# Stiralka.net
KiCad netlist of a schematic drawn in Altium Designer
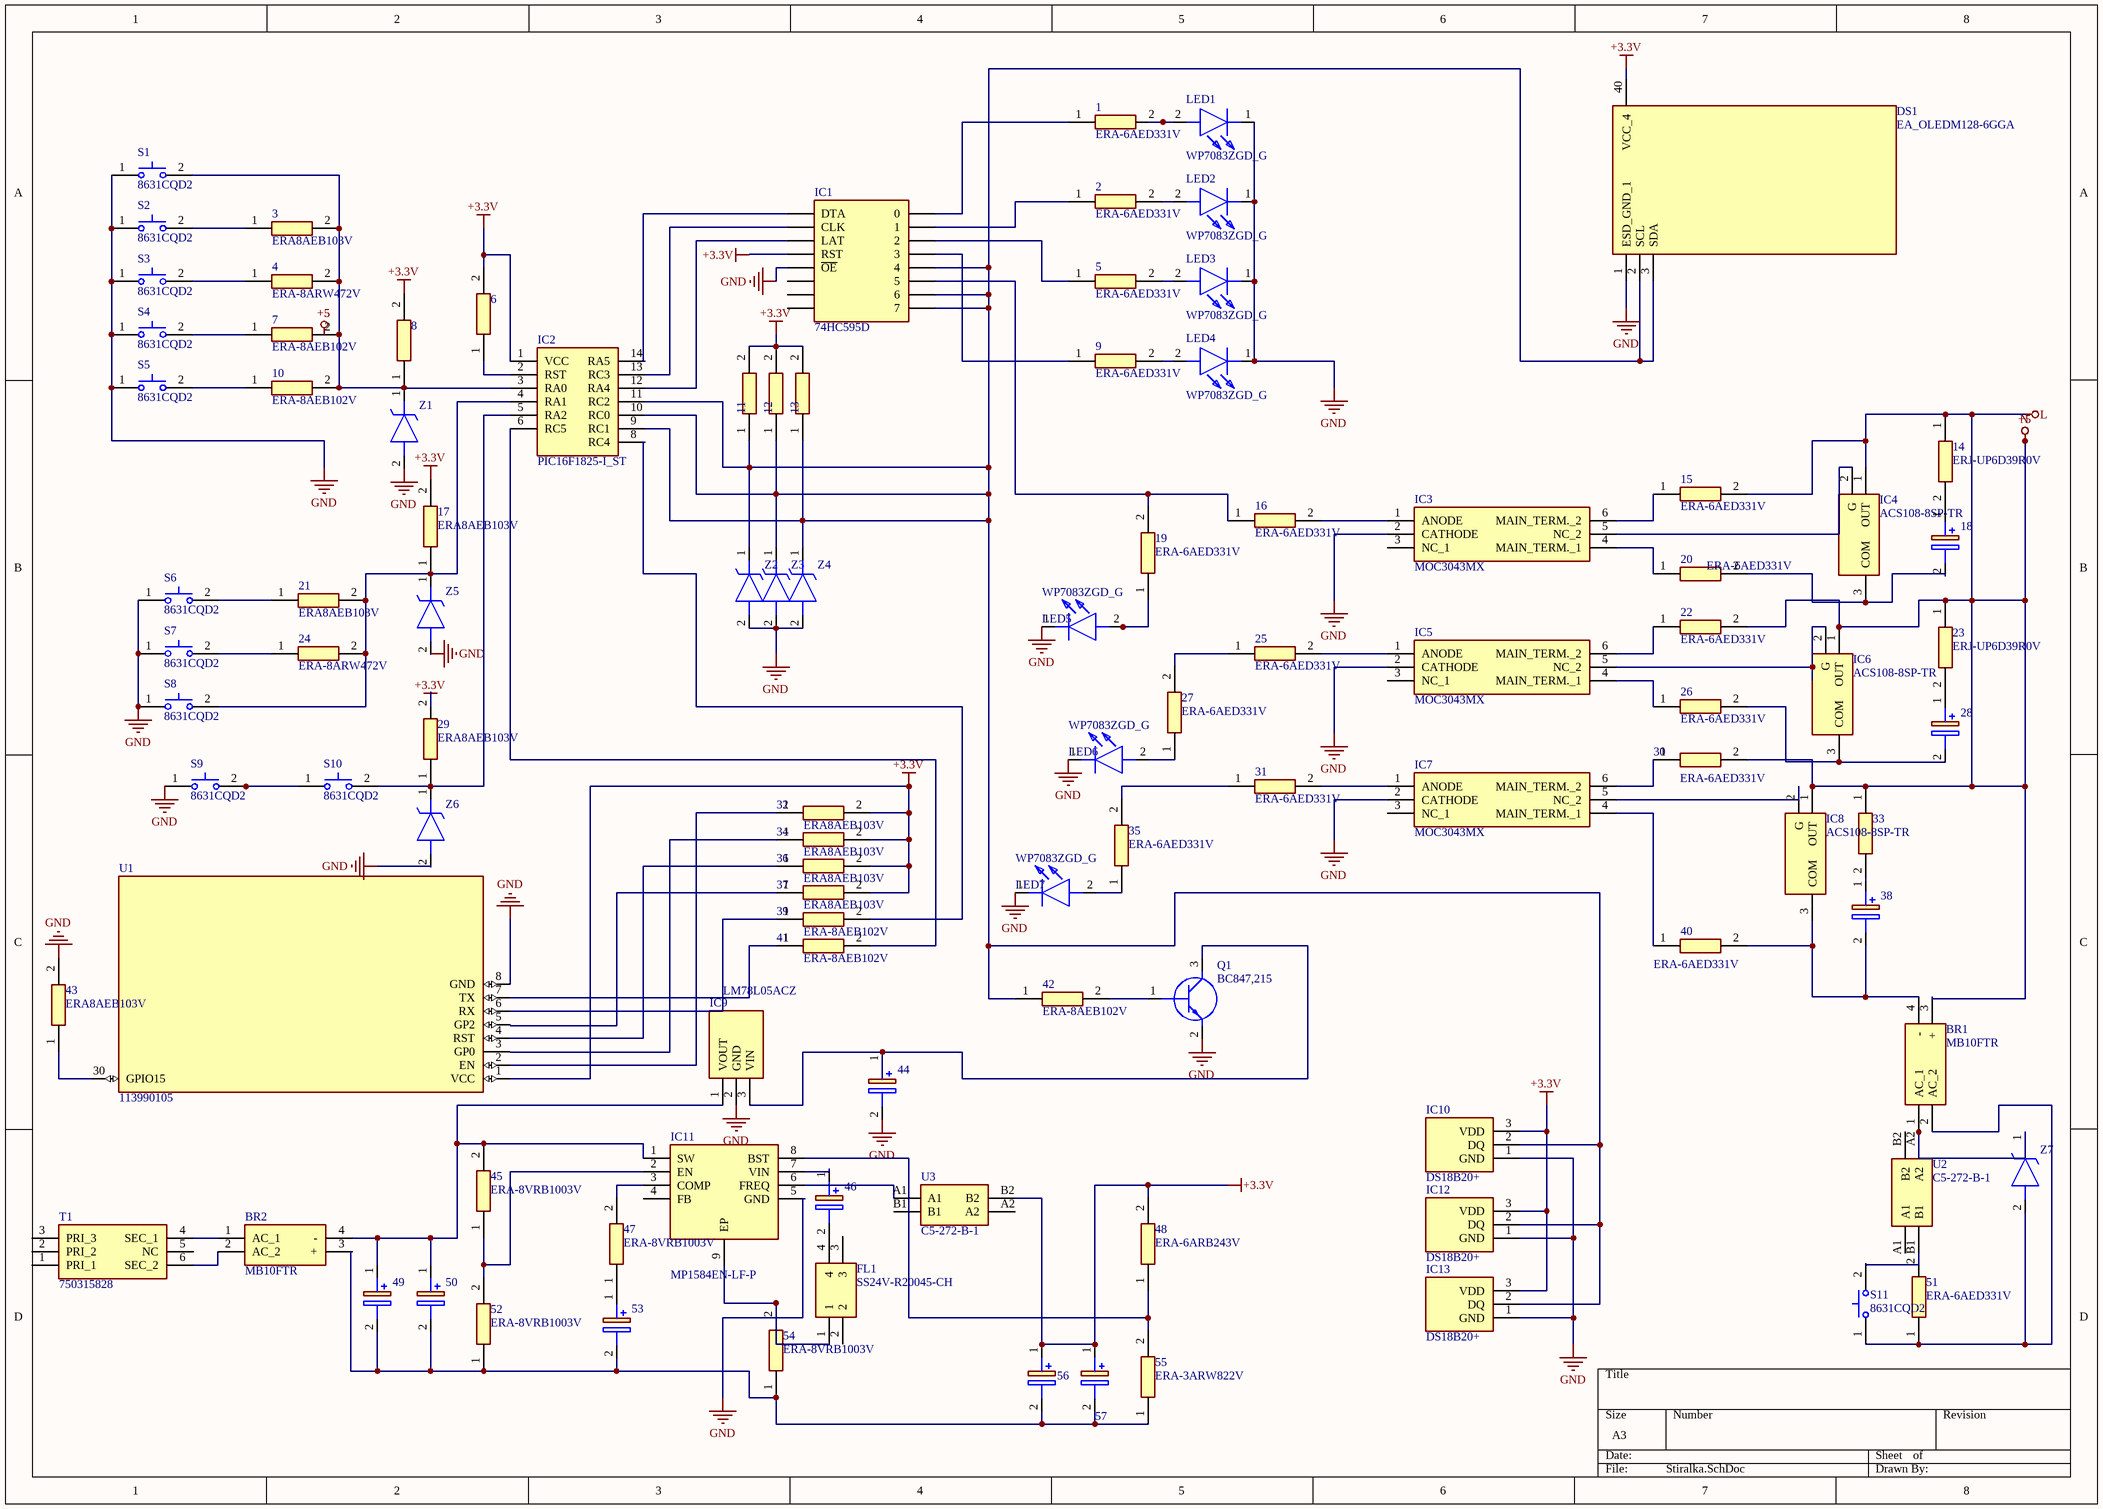
[diagram p0: Stiralka.SchDoc]

(export (version "E")
  (design (tool "Eeschema 10.0.6"))
  (components
    (comp (ref "1")
      (value "ERA-6AED331V")
      (footprint "SamacSys:ERA6AEB1020V")
      (description "Resistor")
      (fields (field (name "MOUSER PART NUMBER") "667-ERA-6AED331V"))
      (libsource (lib "*") (part "ERA-6AED331V"))
    )
    (comp (ref "2")
      (value "ERA-6AED331V")
      (footprint "SamacSys:ERA6AEB1020V")
      (description "Resistor")
      (fields (field (name "MOUSER PART NUMBER") "667-ERA-6AED331V"))
      (libsource (lib "*") (part "ERA-6AED331V"))
    )
    (comp (ref "3")
      (value "ERA8AEB103V")
      (footprint "SamacSys:RESC3216X70N")
      (description "Resistor")
      (libsource (lib "*") (part "ERA8AEB103V"))
    )
    (comp (ref "4")
      (value "ERA-8ARW472V")
      (footprint "SamacSys:RESC3216X70N")
      (description "Resistor")
      (fields (field (name "MOUSER PART NUMBER") "667-ERA-8ARW472V"))
      (libsource (lib "*") (part "ERA-8ARW472V"))
    )
    (comp (ref "5")
      (value "ERA-6AED331V")
      (footprint "SamacSys:ERA6AEB1020V")
      (description "Resistor")
      (fields (field (name "MOUSER PART NUMBER") "667-ERA-6AED331V"))
      (libsource (lib "*") (part "ERA-6AED331V"))
    )
    (comp (ref "6")
      (value "ERA8AEB103V")
      (footprint "SamacSys:RESC3216X70N")
      (description "Resistor")
      (libsource (lib "") (part "ERA8AEB103V_1"))
    )
    (comp (ref "7")
      (value "ERA-8AEB102V")
      (footprint "SamacSys:RESC3216X70N")
      (description "Resistor")
      (fields (field (name "MOUSER PART NUMBER") "667-ERA-8AEB102V"))
      (libsource (lib "*") (part "ERA-8AEB102V"))
    )
    (comp (ref "8")
      (value "ERA8AEB103V")
      (footprint "SamacSys:RESC3216X70N")
      (description "Resistor")
      (libsource (lib "") (part "ERA8AEB103V_1"))
    )
    (comp (ref "9")
      (value "ERA-6AED331V")
      (footprint "SamacSys:ERA6AEB1020V")
      (description "Resistor")
      (fields (field (name "MOUSER PART NUMBER") "667-ERA-6AED331V"))
      (libsource (lib "*") (part "ERA-6AED331V"))
    )
    (comp (ref "10")
      (value "ERA-8AEB102V")
      (footprint "SamacSys:RESC3216X70N")
      (description "Resistor")
      (fields (field (name "MOUSER PART NUMBER") "667-ERA-8AEB102V"))
      (libsource (lib "*") (part "ERA-8AEB102V"))
    )
    (comp (ref "11")
      (value "RA-8ARW472V")
      (footprint "SamacSys:RESC3216X70N")
      (description "Resistor")
      (fields
        (field (name "MANUFACTURER_PART_NUMBER") "ERA-8ARW472V")
        (field (name "MOUSER PART NUMBER") "667-ERA-8ARW472V")
      )
      (libsource (lib "") (part "ERA-8ARW472V_1"))
    )
    (comp (ref "12")
      (value "ERA-8ARW472V")
      (footprint "SamacSys:RESC3216X70N")
      (description "Resistor")
      (fields (field (name "MOUSER PART NUMBER") "667-ERA-8ARW472V"))
      (libsource (lib "") (part "ERA-8ARW472V_1"))
    )
    (comp (ref "13")
      (value "ERA-8ARW472V")
      (footprint "SamacSys:RESC3216X70N")
      (description "Resistor")
      (fields (field (name "MOUSER PART NUMBER") "667-ERA-8ARW472V"))
      (libsource (lib "") (part "ERA-8ARW472V_1"))
    )
    (comp (ref "14")
      (value "ERJ-UP6D39R0V")
      (footprint "SamacSys:ERJUP6")
      (description "Resistor")
      (libsource (lib "*") (part "ERJ-UP6D39R0V"))
    )
    (comp (ref "15")
      (value "ERA-6AED331V")
      (footprint "SamacSys:ERA6AEB1020V")
      (description "Resistor")
      (fields (field (name "MOUSER PART NUMBER") "667-ERA-6AED331V"))
      (libsource (lib "*") (part "ERA-6AED331V"))
    )
    (comp (ref "16")
      (value "ERA-6AED331V")
      (footprint "SamacSys:ERA6AEB1020V")
      (description "Resistor")
      (fields (field (name "MOUSER PART NUMBER") "667-ERA-6AED331V"))
      (libsource (lib "*") (part "ERA-6AED331V"))
    )
    (comp (ref "17")
      (value "ERA8AEB103V")
      (footprint "SamacSys:RESC3216X70N")
      (description "Resistor")
      (libsource (lib "") (part "ERA8AEB103V_1"))
    )
    (comp (ref "18")
      (value "UWP1H0R1MCL1GB")
      (footprint "SamacSys:CAPAE430X550N")
      (description "Capacitor Polarised")
      (fields (field (name "MOUSER PART NUMBER") "647-UWP1H0R1MCL"))
      (libsource (lib "*") (part "UWP1H0R1MCL1GB"))
    )
    (comp (ref "19")
      (value "ERA-6AED331V")
      (footprint "SamacSys:ERA6AEB1020V")
      (description "Resistor")
      (fields (field (name "MOUSER PART NUMBER") "667-ERA-6AED331V"))
      (libsource (lib "") (part "ERA-6AED331V_1"))
    )
    (comp (ref "20")
      (value "ERA-6AED331V")
      (footprint "SamacSys:ERA6AEB1020V")
      (description "Resistor")
      (fields (field (name "MOUSER PART NUMBER") "667-ERA-6AED331V"))
      (libsource (lib "*") (part "ERA-6AED331V"))
    )
    (comp (ref "21")
      (value "ERA8AEB103V")
      (footprint "SamacSys:RESC3216X70N")
      (description "Resistor")
      (libsource (lib "*") (part "ERA8AEB103V"))
    )
    (comp (ref "22")
      (value "ERA-6AED331V")
      (footprint "SamacSys:ERA6AEB1020V")
      (description "Resistor")
      (fields (field (name "MOUSER PART NUMBER") "667-ERA-6AED331V"))
      (libsource (lib "*") (part "ERA-6AED331V"))
    )
    (comp (ref "23")
      (value "ERJ-UP6D39R0V")
      (footprint "SamacSys:ERJUP6")
      (description "Resistor")
      (libsource (lib "*") (part "ERJ-UP6D39R0V"))
    )
    (comp (ref "24")
      (value "ERA-8ARW472V")
      (footprint "SamacSys:RESC3216X70N")
      (description "Resistor")
      (fields (field (name "MOUSER PART NUMBER") "667-ERA-8ARW472V"))
      (libsource (lib "*") (part "ERA-8ARW472V"))
    )
    (comp (ref "25")
      (value "ERA-6AED331V")
      (footprint "SamacSys:ERA6AEB1020V")
      (description "Resistor")
      (fields (field (name "MOUSER PART NUMBER") "667-ERA-6AED331V"))
      (libsource (lib "*") (part "ERA-6AED331V"))
    )
    (comp (ref "26")
      (value "ERA-6AED331V")
      (footprint "SamacSys:ERA6AEB1020V")
      (description "Resistor")
      (fields (field (name "MOUSER PART NUMBER") "667-ERA-6AED331V"))
      (libsource (lib "*") (part "ERA-6AED331V"))
    )
    (comp (ref "27")
      (value "ERA-6AED331V")
      (footprint "SamacSys:ERA6AEB1020V")
      (description "Resistor")
      (fields (field (name "MOUSER PART NUMBER") "667-ERA-6AED331V"))
      (libsource (lib "") (part "ERA-6AED331V_1"))
    )
    (comp (ref "28")
      (value "UWP1H0R1MCL1GB")
      (footprint "SamacSys:CAPAE430X550N")
      (description "Capacitor Polarised")
      (fields (field (name "MOUSER PART NUMBER") "647-UWP1H0R1MCL"))
      (libsource (lib "*") (part "UWP1H0R1MCL1GB"))
    )
    (comp (ref "29")
      (value "ERA8AEB103V")
      (footprint "SamacSys:RESC3216X70N")
      (description "Resistor")
      (libsource (lib "") (part "ERA8AEB103V_1"))
    )
    (comp (ref "30")
      (value "ERA-6AED331V")
      (footprint "SamacSys:ERA6AEB1020V")
      (description "Resistor")
      (fields (field (name "MOUSER PART NUMBER") "667-ERA-6AED331V"))
      (libsource (lib "*") (part "ERA-6AED331V"))
    )
    (comp (ref "31")
      (value "ERA-6AED331V")
      (footprint "SamacSys:ERA6AEB1020V")
      (description "Resistor")
      (fields (field (name "MOUSER PART NUMBER") "667-ERA-6AED331V"))
      (libsource (lib "*") (part "ERA-6AED331V"))
    )
    (comp (ref "32")
      (value "ERA8AEB103V")
      (footprint "SamacSys:RESC3216X70N")
      (description "Resistor")
      (libsource (lib "*") (part "ERA8AEB103V"))
    )
    (comp (ref "33")
      (value "ERJ-UP6D39R0V")
      (footprint "SamacSys:ERJUP6")
      (description "Resistor")
      (libsource (lib "*") (part "ERJ-UP6D39R0V"))
    )
    (comp (ref "34")
      (value "ERA8AEB103V")
      (footprint "SamacSys:RESC3216X70N")
      (description "Resistor")
      (libsource (lib "*") (part "ERA8AEB103V"))
    )
    (comp (ref "35")
      (value "ERA-6AED331V")
      (footprint "SamacSys:ERA6AEB1020V")
      (description "Resistor")
      (fields (field (name "MOUSER PART NUMBER") "667-ERA-6AED331V"))
      (libsource (lib "") (part "ERA-6AED331V_1"))
    )
    (comp (ref "36")
      (value "ERA8AEB103V")
      (footprint "SamacSys:RESC3216X70N")
      (description "Resistor")
      (libsource (lib "*") (part "ERA8AEB103V"))
    )
    (comp (ref "37")
      (value "ERA8AEB103V")
      (footprint "SamacSys:RESC3216X70N")
      (description "Resistor")
      (libsource (lib "*") (part "ERA8AEB103V"))
    )
    (comp (ref "38")
      (value "UWP1H0R1MCL1GB")
      (footprint "SamacSys:CAPAE430X550N")
      (description "Capacitor Polarised")
      (fields (field (name "MOUSER PART NUMBER") "647-UWP1H0R1MCL"))
      (libsource (lib "*") (part "UWP1H0R1MCL1GB"))
    )
    (comp (ref "39")
      (value "ERA-8AEB102V")
      (footprint "SamacSys:RESC3216X70N")
      (description "Resistor")
      (fields (field (name "MOUSER PART NUMBER") "667-ERA-8AEB102V"))
      (libsource (lib "*") (part "ERA-8AEB102V"))
    )
    (comp (ref "40")
      (value "ERA-6AED331V")
      (footprint "SamacSys:ERA6AEB1020V")
      (description "Resistor")
      (fields (field (name "MOUSER PART NUMBER") "667-ERA-6AED331V"))
      (libsource (lib "*") (part "ERA-6AED331V"))
    )
    (comp (ref "41")
      (value "ERA-8AEB102V")
      (footprint "SamacSys:RESC3216X70N")
      (description "Resistor")
      (fields (field (name "MOUSER PART NUMBER") "667-ERA-8AEB102V"))
      (libsource (lib "*") (part "ERA-8AEB102V"))
    )
    (comp (ref "42")
      (value "ERA-8AEB102V")
      (footprint "SamacSys:RESC3216X70N")
      (description "Resistor")
      (fields (field (name "MOUSER PART NUMBER") "667-ERA-8AEB102V"))
      (libsource (lib "*") (part "ERA-8AEB102V"))
    )
    (comp (ref "43")
      (value "ERA8AEB103V")
      (footprint "SamacSys:RESC3216X70N")
      (description "Resistor")
      (libsource (lib "") (part "ERA8AEB103V_1"))
    )
    (comp (ref "44")
      (value "EEE-FN1H100UR")
      (footprint "SamacSys:EEE1AA220WR")
      (description "Capacitor Polarised")
      (fields (field (name "MOUSER PART NUMBER") "667-EEE-FN1H100UR"))
      (libsource (lib "*") (part "EEE-FN1H100UR"))
    )
    (comp (ref "45")
      (value "ERA-8VRB1003V")
      (footprint "SamacSys:ERA8KEB1004V")
      (description "Resistor")
      (fields (field (name "MOUSER PART NUMBER") "667-ERA-8VRB1003V"))
      (libsource (lib "*") (part "ERA-8VRB1003V"))
    )
    (comp (ref "46")
      (value "EEE-FN1H100UR")
      (footprint "SamacSys:EEE1AA220WR")
      (description "Capacitor Polarised")
      (fields (field (name "MOUSER PART NUMBER") "667-EEE-FN1H100UR"))
      (libsource (lib "*") (part "EEE-FN1H100UR"))
    )
    (comp (ref "47")
      (value "ERA-8VRB1003V")
      (footprint "SamacSys:ERA8KEB1004V")
      (description "Resistor")
      (fields (field (name "MOUSER PART NUMBER") "667-ERA-8VRB1003V"))
      (libsource (lib "*") (part "ERA-8VRB1003V"))
    )
    (comp (ref "48")
      (value "ERA-6ARB243V")
      (footprint "SamacSys:ERA6AEB1020V")
      (description "Resistor")
      (fields (field (name "MOUSER PART NUMBER") "667-ERA-6ARB243V"))
      (libsource (lib "*") (part "ERA-6ARB243V"))
    )
    (comp (ref "49")
      (value "EEE-FN1H100UR")
      (footprint "SamacSys:EEE1AA220WR")
      (description "Capacitor Polarised")
      (fields (field (name "MOUSER PART NUMBER") "667-EEE-FN1H100UR"))
      (libsource (lib "*") (part "EEE-FN1H100UR"))
    )
    (comp (ref "50")
      (value "EEE-FT1C102AP")
      (footprint "SamacSys:EEE0JA152UAP")
      (description "Capacitor Polarised")
      (fields (field (name "MOUSER PART NUMBER") "667-EEE-FT1C102AP"))
      (libsource (lib "*") (part "EEE-FT1C102AP"))
    )
    (comp (ref "51")
      (value "ERA-6AED331V")
      (footprint "SamacSys:ERA6AEB1020V")
      (description "Resistor")
      (fields (field (name "MOUSER PART NUMBER") "667-ERA-6AED331V"))
      (libsource (lib "") (part "ERA-6AED331V_1"))
    )
    (comp (ref "52")
      (value "ERA-8VRB1003V")
      (footprint "SamacSys:ERA8KEB1004V")
      (description "Resistor")
      (fields (field (name "MOUSER PART NUMBER") "667-ERA-8VRB1003V"))
      (libsource (lib "*") (part "ERA-8VRB1003V"))
    )
    (comp (ref "53")
      (value "EEE-FN1H100UR")
      (footprint "SamacSys:EEE1AA220WR")
      (description "Capacitor Polarised")
      (fields (field (name "MOUSER PART NUMBER") "667-EEE-FN1H100UR"))
      (libsource (lib "*") (part "EEE-FN1H100UR"))
    )
    (comp (ref "54")
      (value "ERA-8VRB1003V")
      (footprint "SamacSys:ERA8KEB1004V")
      (description "Resistor")
      (fields (field (name "MOUSER PART NUMBER") "667-ERA-8VRB1003V"))
      (libsource (lib "*") (part "ERA-8VRB1003V"))
    )
    (comp (ref "55")
      (value "ERA-3ARW822V")
      (footprint "SamacSys:ERA3AEB101V")
      (description "Resistor")
      (fields (field (name "MOUSER PART NUMBER") "667-ERA-3ARW822V"))
      (libsource (lib "*") (part "ERA-3ARW822V"))
    )
    (comp (ref "56")
      (value "EEE-FN1H100UR")
      (footprint "SamacSys:EEE1AA220WR")
      (description "Capacitor Polarised")
      (fields (field (name "MOUSER PART NUMBER") "667-EEE-FN1H100UR"))
      (libsource (lib "*") (part "EEE-FN1H100UR"))
    )
    (comp (ref "57")
      (value "EEE-FT1C102AP")
      (footprint "SamacSys:EEE0JA152UAP")
      (description "Capacitor Polarised")
      (fields (field (name "MOUSER PART NUMBER") "667-EEE-FT1C102AP"))
      (libsource (lib "*") (part "EEE-FT1C102AP"))
    )
    (comp (ref "BR1")
      (value "MB10FTR")
      (footprint "SamacSys:SOP250P670X160-4N")
      (description "Bridge Rectifier")
      (libsource (lib "*") (part "MB10FTR"))
    )
    (comp (ref "BR2")
      (value "MB10FTR")
      (footprint "SamacSys:SOP250P670X160-4N")
      (description "Bridge Rectifier")
      (libsource (lib "") (part "MB10FTR_1"))
    )
    (comp (ref "DS1")
      (value "EA_OLEDM128-6GGA")
      (footprint "SamacSys:EAOLEDM1286GGA")
      (description "Display")
      (fields
        (field (name "MANUFACTURER_PART_NUMBER") "EA OLEDM128-6GGA")
        (field (name "MOUSER PART NUMBER") "790-EAOLEDM1286GGA")
      )
      (libsource (lib "*") (part "EA_OLEDM128-6GGA"))
    )
    (comp (ref "FL1")
      (value "SS24V-R20045-CH")
      (footprint "SamacSys:SS24VR20045CH")
      (description "Filter")
      (fields (field (name "MOUSER PART NUMBER") "80-SS24V-R20045-CH"))
      (libsource (lib "*") (part "SS24V-R20045-CH"))
    )
    (comp (ref "IC1")
      (value "74HC595D")
      (footprint "SamacSys:SOIC127P600X175-16N")
      (description "Integrated Circuit")
      (libsource (lib "*") (part "74HC595D"))
    )
    (comp (ref "IC2")
      (value "PIC16F1825-I_ST")
      (footprint "SamacSys:SOP65P640X120-14N")
      (description "Integrated Circuit")
      (fields
        (field (name "MANUFACTURER_PART_NUMBER") "PIC16F1825-I/ST")
        (field (name "MOUSER PART NUMBER") "579-PIC16F1825-I/ST")
      )
      (libsource (lib "*") (part "PIC16F1825-I_ST"))
    )
    (comp (ref "IC3")
      (value "MOC3043MX")
      (footprint "SamacSys:DIP762W51P254L851H508Q6N")
      (description "Integrated Circuit")
      (libsource (lib "*") (part "MOC3043MX"))
    )
    (comp (ref "IC4")
      (value "ACS108-8SP-TR")
      (footprint "SamacSys:ACS1088SPTR")
      (description "Integrated Circuit")
      (fields (field (name "MOUSER PART NUMBER") "511-ACS108-8SP-TR"))
      (libsource (lib "*") (part "ACS108-8SP-TR"))
    )
    (comp (ref "IC5")
      (value "MOC3043MX")
      (footprint "SamacSys:DIP762W51P254L851H508Q6N")
      (description "Integrated Circuit")
      (libsource (lib "*") (part "MOC3043MX"))
    )
    (comp (ref "IC6")
      (value "ACS108-8SP-TR")
      (footprint "SamacSys:ACS1088SPTR")
      (description "Integrated Circuit")
      (fields (field (name "MOUSER PART NUMBER") "511-ACS108-8SP-TR"))
      (libsource (lib "*") (part "ACS108-8SP-TR"))
    )
    (comp (ref "IC7")
      (value "MOC3043MX")
      (footprint "SamacSys:DIP762W51P254L851H508Q6N")
      (description "Integrated Circuit")
      (libsource (lib "*") (part "MOC3043MX"))
    )
    (comp (ref "IC8")
      (value "ACS108-8SP-TR")
      (footprint "SamacSys:ACS1088SPTR")
      (description "Integrated Circuit")
      (fields (field (name "MOUSER PART NUMBER") "511-ACS108-8SP-TR"))
      (libsource (lib "*") (part "ACS108-8SP-TR"))
    )
    (comp (ref "IC9")
      (value "LM78L05ACZ")
      (footprint "SamacSys:LM78L05ACZ")
      (description "Integrated Circuit")
      (fields (field (name "MOUSER PART NUMBER") "926-LM78L05ACZ"))
      (libsource (lib "*") (part "LM78L05ACZ"))
    )
    (comp (ref "IC10")
      (value "DS18B20+")
      (footprint "SamacSys:DS18B20")
      (description "Integrated Circuit")
      (fields (field (name "MOUSER PART NUMBER") "700-DS18B20+"))
      (libsource (lib "*") (part "DS18B20+"))
    )
    (comp (ref "IC11")
      (value "MP1584EN-LF-P")
      (footprint "SamacSys:SOIC127P600X170-9N")
      (description "Integrated Circuit")
      (fields (field (name "MOUSER PART NUMBER") "946-MP1584EN-LF-P"))
      (libsource (lib "*") (part "MP1584EN-LF-P"))
    )
    (comp (ref "IC12")
      (value "DS18B20+")
      (footprint "SamacSys:DS18B20")
      (description "Integrated Circuit")
      (fields (field (name "MOUSER PART NUMBER") "700-DS18B20+"))
      (libsource (lib "*") (part "DS18B20+"))
    )
    (comp (ref "IC13")
      (value "DS18B20+")
      (footprint "SamacSys:DS18B20")
      (description "Integrated Circuit")
      (fields (field (name "MOUSER PART NUMBER") "700-DS18B20+"))
      (libsource (lib "*") (part "DS18B20+"))
    )
    (comp (ref "LED1")
      (value "WP7083ZGD_G")
      (footprint "SamacSys:L53ND")
      (description "LED")
      (fields
        (field (name "MANUFACTURER_PART_NUMBER") "WP7083ZGD/G")
        (field (name "MOUSER PART NUMBER") "604-WP7083ZGD/G")
      )
      (libsource (lib "*") (part "WP7083ZGD_G"))
    )
    (comp (ref "LED2")
      (value "WP7083ZGD_G")
      (footprint "SamacSys:L53ND")
      (description "LED")
      (fields
        (field (name "MANUFACTURER_PART_NUMBER") "WP7083ZGD/G")
        (field (name "MOUSER PART NUMBER") "604-WP7083ZGD/G")
      )
      (libsource (lib "*") (part "WP7083ZGD_G"))
    )
    (comp (ref "LED3")
      (value "WP7083ZGD_G")
      (footprint "SamacSys:L53ND")
      (description "LED")
      (fields
        (field (name "MANUFACTURER_PART_NUMBER") "WP7083ZGD/G")
        (field (name "MOUSER PART NUMBER") "604-WP7083ZGD/G")
      )
      (libsource (lib "*") (part "WP7083ZGD_G"))
    )
    (comp (ref "LED4")
      (value "WP7083ZGD_G")
      (footprint "SamacSys:L53ND")
      (description "LED")
      (fields
        (field (name "MANUFACTURER_PART_NUMBER") "WP7083ZGD/G")
        (field (name "MOUSER PART NUMBER") "604-WP7083ZGD/G")
      )
      (libsource (lib "*") (part "WP7083ZGD_G"))
    )
    (comp (ref "LED5")
      (value "WP7083ZGD_G")
      (footprint "SamacSys:L53ND")
      (description "LED")
      (fields
        (field (name "MANUFACTURER_PART_NUMBER") "WP7083ZGD/G")
        (field (name "MOUSER PART NUMBER") "604-WP7083ZGD/G")
      )
      (libsource (lib "*") (part "WP7083ZGD_G"))
    )
    (comp (ref "LED6")
      (value "WP7083ZGD_G")
      (footprint "SamacSys:L53ND")
      (description "LED")
      (fields
        (field (name "MANUFACTURER_PART_NUMBER") "WP7083ZGD/G")
        (field (name "MOUSER PART NUMBER") "604-WP7083ZGD/G")
      )
      (libsource (lib "*") (part "WP7083ZGD_G"))
    )
    (comp (ref "LED7")
      (value "WP7083ZGD_G")
      (footprint "SamacSys:L53ND")
      (description "LED")
      (fields
        (field (name "MANUFACTURER_PART_NUMBER") "WP7083ZGD/G")
        (field (name "MOUSER PART NUMBER") "604-WP7083ZGD/G")
      )
      (libsource (lib "*") (part "WP7083ZGD_G"))
    )
    (comp (ref "Q1")
      (value "BC847,215")
      (footprint "SamacSys:BC847215")
      (description "Transistor BJT NPN")
      (fields (field (name "MOUSER PART NUMBER") "771-BC847215"))
      (libsource (lib "*") (part "BC847,215"))
    )
    (comp (ref "S1")
      (value "8631CQD2")
      (footprint "SamacSys:8631CQD2")
      (description "Switch (2-Pin Push)")
      (fields (field (name "MOUSER PART NUMBER") "611-8631-261"))
      (libsource (lib "*") (part "8631CQD2"))
    )
    (comp (ref "S2")
      (value "8631CQD2")
      (footprint "SamacSys:8631CQD2")
      (description "Switch (2-Pin Push)")
      (fields (field (name "MOUSER PART NUMBER") "611-8631-261"))
      (libsource (lib "*") (part "8631CQD2"))
    )
    (comp (ref "S3")
      (value "8631CQD2")
      (footprint "SamacSys:8631CQD2")
      (description "Switch (2-Pin Push)")
      (fields (field (name "MOUSER PART NUMBER") "611-8631-261"))
      (libsource (lib "*") (part "8631CQD2"))
    )
    (comp (ref "S4")
      (value "8631CQD2")
      (footprint "SamacSys:8631CQD2")
      (description "Switch (2-Pin Push)")
      (fields (field (name "MOUSER PART NUMBER") "611-8631-261"))
      (libsource (lib "*") (part "8631CQD2"))
    )
    (comp (ref "S5")
      (value "8631CQD2")
      (footprint "SamacSys:8631CQD2")
      (description "Switch (2-Pin Push)")
      (fields (field (name "MOUSER PART NUMBER") "611-8631-261"))
      (libsource (lib "*") (part "8631CQD2"))
    )
    (comp (ref "S6")
      (value "8631CQD2")
      (footprint "SamacSys:8631CQD2")
      (description "Switch (2-Pin Push)")
      (fields (field (name "MOUSER PART NUMBER") "611-8631-261"))
      (libsource (lib "*") (part "8631CQD2"))
    )
    (comp (ref "S7")
      (value "8631CQD2")
      (footprint "SamacSys:8631CQD2")
      (description "Switch (2-Pin Push)")
      (fields (field (name "MOUSER PART NUMBER") "611-8631-261"))
      (libsource (lib "*") (part "8631CQD2"))
    )
    (comp (ref "S8")
      (value "8631CQD2")
      (footprint "SamacSys:8631CQD2")
      (description "Switch (2-Pin Push)")
      (fields (field (name "MOUSER PART NUMBER") "611-8631-261"))
      (libsource (lib "*") (part "8631CQD2"))
    )
    (comp (ref "S9")
      (value "8631CQD2")
      (footprint "SamacSys:8631CQD2")
      (description "Switch (2-Pin Push)")
      (fields (field (name "MOUSER PART NUMBER") "611-8631-261"))
      (libsource (lib "*") (part "8631CQD2"))
    )
    (comp (ref "S10")
      (value "8631CQD2")
      (footprint "SamacSys:8631CQD2")
      (description "Switch (2-Pin Push)")
      (fields (field (name "MOUSER PART NUMBER") "611-8631-261"))
      (libsource (lib "*") (part "8631CQD2"))
    )
    (comp (ref "S11")
      (value "8631CQD2")
      (footprint "SamacSys:8631CQD2")
      (description "Switch (2-Pin Push)")
      (fields (field (name "MOUSER PART NUMBER") "611-8631-261"))
      (libsource (lib "*") (part "8631CQD2"))
    )
    (comp (ref "T1")
      (value "750315828")
      (footprint "SamacSys:750315828")
      (description "Transformer")
      (fields (field (name "MOUSER PART NUMBER") "710-750315828"))
      (libsource (lib "*") (part "750315828"))
    )
    (comp (ref "U1")
      (value "113990105")
      (footprint "SamacSys:113990105")
      (description "Undefined or Miscellaneous")
      (fields (field (name "MOUSER PART NUMBER") "713-113990105"))
      (libsource (lib "*") (part "113990105"))
    )
    (comp (ref "U2")
      (value "C5-272-B-1")
      (footprint "SamacSys:C5272B1")
      (description "Undefined or Miscellaneous")
      (libsource (lib "*") (part "C5-272-B-1"))
    )
    (comp (ref "U3")
      (value "C5-272-B-1")
      (footprint "SamacSys:C5272B1")
      (description "Undefined or Miscellaneous")
      (libsource (lib "") (part "C5-272-B-1_1"))
    )
    (comp (ref "Z1")
      (value "SZMM3Z18VT1G")
      (footprint "SamacSys:SOD2512X110N")
      (description "Zener Diode")
      (fields (field (name "MOUSER PART NUMBER") "863-SZMM3Z18VT1G"))
      (libsource (lib "*") (part "SZMM3Z18VT1G"))
    )
    (comp (ref "Z2")
      (value "SZMM3Z18VT1G")
      (footprint "SamacSys:SOD2512X110N")
      (description "Zener Diode")
      (fields (field (name "MOUSER PART NUMBER") "863-SZMM3Z18VT1G"))
      (libsource (lib "*") (part "SZMM3Z18VT1G"))
    )
    (comp (ref "Z3")
      (value "SZMM3Z18VT1G")
      (footprint "SamacSys:SOD2512X110N")
      (description "Zener Diode")
      (fields (field (name "MOUSER PART NUMBER") "863-SZMM3Z18VT1G"))
      (libsource (lib "*") (part "SZMM3Z18VT1G"))
    )
    (comp (ref "Z4")
      (value "SZMM3Z18VT1G")
      (footprint "SamacSys:SOD2512X110N")
      (description "Zener Diode")
      (fields (field (name "MOUSER PART NUMBER") "863-SZMM3Z18VT1G"))
      (libsource (lib "*") (part "SZMM3Z18VT1G"))
    )
    (comp (ref "Z5")
      (value "SZMM3Z18VT1G")
      (footprint "SamacSys:SOD2512X110N")
      (description "Zener Diode")
      (fields (field (name "MOUSER PART NUMBER") "863-SZMM3Z18VT1G"))
      (libsource (lib "*") (part "SZMM3Z18VT1G"))
    )
    (comp (ref "Z6")
      (value "SZMM3Z18VT1G")
      (footprint "SamacSys:SOD2512X110N")
      (description "Zener Diode")
      (fields (field (name "MOUSER PART NUMBER") "863-SZMM3Z18VT1G"))
      (libsource (lib "*") (part "SZMM3Z18VT1G"))
    )
    (comp (ref "Z7")
      (value "SZMM3Z18VT1G")
      (footprint "SamacSys:SOD2512X110N")
      (description "Zener Diode")
      (fields (field (name "MOUSER PART NUMBER") "863-SZMM3Z18VT1G"))
      (libsource (lib "*") (part "SZMM3Z18VT1G"))
    )
  )
  (nets
    (net (code "1") (name "+3.3V") (class "Default")
      (node (ref "11") (pin "2") (pinfunction "2_2") (pintype "passive"))
      (node (ref "12") (pin "2") (pinfunction "2_2") (pintype "passive"))
      (node (ref "13") (pin "2") (pinfunction "2_2") (pintype "passive"))
      (node (ref "17") (pin "2") (pinfunction "2_2") (pintype "passive"))
      (node (ref "29") (pin "2") (pinfunction "2_2") (pintype "passive"))
      (node (ref "32") (pin "2") (pinfunction "2_2") (pintype "passive"))
      (node (ref "34") (pin "2") (pinfunction "2_2") (pintype "passive"))
      (node (ref "36") (pin "2") (pinfunction "2_2") (pintype "passive"))
      (node (ref "37") (pin "2") (pinfunction "2_2") (pintype "passive"))
      (node (ref "48") (pin "2") (pinfunction "2_2") (pintype "passive"))
      (node (ref "56") (pin "1") (pinfunction "+_1") (pintype "passive"))
      (node (ref "57") (pin "1") (pinfunction "+_1") (pintype "passive"))
      (node (ref "6") (pin "2") (pinfunction "2_2") (pintype "passive"))
      (node (ref "8") (pin "2") (pinfunction "2_2") (pintype "passive"))
      (node (ref "DS1") (pin "40") (pinfunction "VCC_4_40") (pintype "passive"))
      (node (ref "IC1") (pin "12") (pinfunction "RST_12") (pintype "passive"))
      (node (ref "IC10") (pin "3") (pinfunction "VDD_3") (pintype "passive"))
      (node (ref "IC12") (pin "3") (pinfunction "VDD_3") (pintype "passive"))
      (node (ref "IC13") (pin "3") (pinfunction "VDD_3") (pintype "passive"))
      (node (ref "IC2") (pin "1") (pinfunction "VCC_1") (pintype "passive"))
      (node (ref "U1") (pin "1") (pinfunction "VCC_1") (pintype "bidirectional"))
      (node (ref "U3") (pin "B2") (pinfunction "B2_B2") (pintype "passive"))
    )
    (net (code "2") (name "+5") (class "Default")
      (node (ref "14") (pin "1") (pinfunction "1_1") (pintype "passive"))
      (node (ref "15") (pin "2") (pinfunction "2_2") (pintype "passive"))
      (node (ref "22") (pin "2") (pinfunction "2_2") (pintype "passive"))
      (node (ref "23") (pin "1") (pinfunction "1_1") (pintype "passive"))
      (node (ref "30") (pin "2") (pinfunction "2_2") (pintype "passive"))
      (node (ref "33") (pin "1") (pinfunction "1_1") (pintype "passive"))
      (node (ref "BR1") (pin "3") (pinfunction "+_3") (pintype "passive"))
      (node (ref "IC4") (pin "1") (pinfunction "OUT_1") (pintype "passive"))
      (node (ref "IC6") (pin "1") (pinfunction "OUT_1") (pintype "passive"))
      (node (ref "IC8") (pin "1") (pinfunction "OUT_1") (pintype "passive"))
    )
    (net (code "3") (name "GND") (class "Default")
      (node (ref "43") (pin "2") (pinfunction "2_2") (pintype "passive"))
      (node (ref "44") (pin "2") (pinfunction "-_2") (pintype "passive"))
      (node (ref "DS1") (pin "1") (pinfunction "ESD_GND_1_1") (pintype "passive"))
      (node (ref "IC1") (pin "13") (pinfunction "~{OE}_13") (pintype "passive"))
      (node (ref "IC10") (pin "1") (pinfunction "GND_1") (pintype "passive"))
      (node (ref "IC11") (pin "5") (pinfunction "GND_5") (pintype "passive"))
      (node (ref "IC12") (pin "1") (pinfunction "GND_1") (pintype "passive"))
      (node (ref "IC13") (pin "1") (pinfunction "GND_1") (pintype "passive"))
      (node (ref "IC3") (pin "2") (pinfunction "CATHODE_2") (pintype "passive"))
      (node (ref "IC5") (pin "2") (pinfunction "CATHODE_2") (pintype "passive"))
      (node (ref "IC7") (pin "2") (pinfunction "CATHODE_2") (pintype "passive"))
      (node (ref "IC9") (pin "2") (pinfunction "GND_2") (pintype "passive"))
      (node (ref "LED1") (pin "1") (pinfunction "K_1") (pintype "passive"))
      (node (ref "LED2") (pin "1") (pinfunction "K_1") (pintype "passive"))
      (node (ref "LED3") (pin "1") (pinfunction "K_1") (pintype "passive"))
      (node (ref "LED4") (pin "1") (pinfunction "K_1") (pintype "passive"))
      (node (ref "LED5") (pin "1") (pinfunction "K_1") (pintype "passive"))
      (node (ref "LED6") (pin "1") (pinfunction "K_1") (pintype "passive"))
      (node (ref "LED7") (pin "1") (pinfunction "K_1") (pintype "passive"))
      (node (ref "Q1") (pin "2") (pinfunction "E_2") (pintype "passive"))
      (node (ref "S1") (pin "1") (pinfunction "N.O._1_1") (pintype "passive"))
      (node (ref "S2") (pin "1") (pinfunction "N.O._1_1") (pintype "passive"))
      (node (ref "S3") (pin "1") (pinfunction "N.O._1_1") (pintype "passive"))
      (node (ref "S4") (pin "1") (pinfunction "N.O._1_1") (pintype "passive"))
      (node (ref "S5") (pin "1") (pinfunction "N.O._1_1") (pintype "passive"))
      (node (ref "S6") (pin "1") (pinfunction "N.O._1_1") (pintype "passive"))
      (node (ref "S7") (pin "1") (pinfunction "N.O._1_1") (pintype "passive"))
      (node (ref "S8") (pin "1") (pinfunction "N.O._1_1") (pintype "passive"))
      (node (ref "S9") (pin "1") (pinfunction "N.O._1_1") (pintype "passive"))
      (node (ref "U1") (pin "8") (pinfunction "GND_8") (pintype "bidirectional"))
      (node (ref "Z1") (pin "2") (pinfunction "A_2") (pintype "passive"))
      (node (ref "Z2") (pin "2") (pinfunction "A_2") (pintype "passive"))
      (node (ref "Z3") (pin "2") (pinfunction "A_2") (pintype "passive"))
      (node (ref "Z4") (pin "2") (pinfunction "A_2") (pintype "passive"))
      (node (ref "Z5") (pin "2") (pinfunction "A_2") (pintype "passive"))
      (node (ref "Z6") (pin "2") (pinfunction "A_2") (pintype "passive"))
    )
    (net (code "4") (name "GND_1") (class "Default")
      (node (ref "U1") (pin "10") (pinfunction "GND_1_10") (pintype "power_in"))
    )
    (net (code "5") (name "GND_2") (class "Default")
      (node (ref "U1") (pin "14") (pinfunction "GND_2_14") (pintype "power_in"))
    )
    (net (code "6") (name "GND_3") (class "Default")
      (node (ref "U1") (pin "17") (pinfunction "GND_3_17") (pintype "power_in"))
    )
    (net (code "7") (name "GND_4") (class "Default")
      (node (ref "U1") (pin "24") (pinfunction "GND_4_24") (pintype "power_in"))
    )
    (net (code "8") (name "Net-(18-+)") (class "Default")
      (node (ref "14") (pin "2") (pinfunction "2_2") (pintype "passive"))
      (node (ref "18") (pin "1") (pinfunction "+_1") (pintype "passive"))
    )
    (net (code "9") (name "Net-(18--)") (class "Default")
      (node (ref "18") (pin "2") (pinfunction "-_2") (pintype "passive"))
      (node (ref "20") (pin "2") (pinfunction "2_2") (pintype "passive"))
      (node (ref "IC4") (pin "3") (pinfunction "COM_3") (pintype "passive"))
    )
    (net (code "10") (name "Net-(25-Pad1)") (class "Default")
      (node (ref "25") (pin "1") (pinfunction "1_1") (pintype "passive"))
      (node (ref "27") (pin "2") (pinfunction "2_2") (pintype "passive"))
    )
    (net (code "11") (name "Net-(28-+)") (class "Default")
      (node (ref "23") (pin "2") (pinfunction "2_2") (pintype "passive"))
      (node (ref "28") (pin "1") (pinfunction "+_1") (pintype "passive"))
    )
    (net (code "12") (name "Net-(28--)") (class "Default")
      (node (ref "26") (pin "2") (pinfunction "2_2") (pintype "passive"))
      (node (ref "28") (pin "2") (pinfunction "-_2") (pintype "passive"))
      (node (ref "IC6") (pin "3") (pinfunction "COM_3") (pintype "passive"))
    )
    (net (code "13") (name "Net-(31-Pad1)") (class "Default")
      (node (ref "31") (pin "1") (pinfunction "1_1") (pintype "passive"))
      (node (ref "35") (pin "2") (pinfunction "2_2") (pintype "passive"))
    )
    (net (code "14") (name "Net-(32-Pad1)") (class "Default")
      (node (ref "32") (pin "1") (pinfunction "1_1") (pintype "passive"))
      (node (ref "U1") (pin "2") (pinfunction "EN_2") (pintype "bidirectional"))
    )
    (net (code "15") (name "Net-(38-+)") (class "Default")
      (node (ref "33") (pin "2") (pinfunction "2_2") (pintype "passive"))
      (node (ref "38") (pin "1") (pinfunction "+_1") (pintype "passive"))
    )
    (net (code "16") (name "Net-(38--)") (class "Default")
      (node (ref "38") (pin "2") (pinfunction "-_2") (pintype "passive"))
      (node (ref "40") (pin "2") (pinfunction "2_2") (pintype "passive"))
      (node (ref "BR1") (pin "4") (pinfunction "-_4") (pintype "passive"))
      (node (ref "IC8") (pin "3") (pinfunction "COM_3") (pintype "passive"))
    )
    (net (code "17") (name "Net-(44-+)") (class "Default")
      (node (ref "44") (pin "1") (pinfunction "+_1") (pintype "passive"))
      (node (ref "IC9") (pin "3") (pinfunction "VIN_3") (pintype "passive"))
      (node (ref "Q1") (pin "3") (pinfunction "C_3") (pintype "passive"))
    )
    (net (code "18") (name "Net-(46-+)") (class "Default")
      (node (ref "46") (pin "1") (pinfunction "+_1") (pintype "passive"))
      (node (ref "IC11") (pin "7") (pinfunction "VIN_7") (pintype "passive"))
    )
    (net (code "19") (name "Net-(46--)") (class "Default")
      (node (ref "46") (pin "2") (pinfunction "-_2") (pintype "passive"))
      (node (ref "FL1") (pin "4") (pinfunction "4_4") (pintype "passive"))
    )
    (net (code "20") (name "Net-(49-+)") (class "Default")
      (node (ref "45") (pin "2") (pinfunction "2_2") (pintype "passive"))
      (node (ref "49") (pin "1") (pinfunction "+_1") (pintype "passive"))
      (node (ref "50") (pin "1") (pinfunction "+_1") (pintype "passive"))
      (node (ref "BR2") (pin "4") (pinfunction "-_4") (pintype "passive"))
      (node (ref "IC11") (pin "1") (pinfunction "SW_1") (pintype "passive"))
      (node (ref "IC9") (pin "1") (pinfunction "VOUT_1") (pintype "passive"))
    )
    (net (code "21") (name "Net-(49--)") (class "Default")
      (node (ref "49") (pin "2") (pinfunction "-_2") (pintype "passive"))
      (node (ref "50") (pin "2") (pinfunction "-_2") (pintype "passive"))
      (node (ref "52") (pin "1") (pinfunction "1_1") (pintype "passive"))
      (node (ref "53") (pin "2") (pinfunction "-_2") (pintype "passive"))
      (node (ref "54") (pin "1") (pinfunction "1_1") (pintype "passive"))
      (node (ref "55") (pin "1") (pinfunction "1_1") (pintype "passive"))
      (node (ref "56") (pin "2") (pinfunction "-_2") (pintype "passive"))
      (node (ref "57") (pin "2") (pinfunction "-_2") (pintype "passive"))
      (node (ref "BR2") (pin "3") (pinfunction "+_3") (pintype "passive"))
    )
    (net (code "22") (name "Net-(53-+)") (class "Default")
      (node (ref "47") (pin "1") (pinfunction "1_1") (pintype "passive"))
      (node (ref "53") (pin "1") (pinfunction "+_1") (pintype "passive"))
    )
    (net (code "23") (name "Net-(BR1-AC_1)") (class "Default")
      (node (ref "BR1") (pin "1") (pinfunction "AC_1_1") (pintype "passive"))
      (node (ref "U2") (pin "A2") (pinfunction "A2_A2") (pintype "passive"))
      (node (ref "Z7") (pin "1") (pinfunction "K_1") (pintype "passive"))
    )
    (net (code "24") (name "Net-(BR1-AC_2)") (class "Default")
      (node (ref "51") (pin "1") (pinfunction "1_1") (pintype "passive"))
      (node (ref "BR1") (pin "2") (pinfunction "AC_2_2") (pintype "passive"))
      (node (ref "S11") (pin "1") (pinfunction "N.O._1_1") (pintype "passive"))
      (node (ref "Z7") (pin "2") (pinfunction "A_2") (pintype "passive"))
    )
    (net (code "25") (name "Net-(BR2-AC_1)") (class "Default")
      (node (ref "BR2") (pin "1") (pinfunction "AC_1_1") (pintype "passive"))
      (node (ref "T1") (pin "4") (pinfunction "SEC_1_4") (pintype "passive"))
    )
    (net (code "26") (name "Net-(BR2-AC_2)") (class "Default")
      (node (ref "BR2") (pin "2") (pinfunction "AC_2_2") (pintype "passive"))
      (node (ref "T1") (pin "6") (pinfunction "SEC_2_6") (pintype "passive"))
    )
    (net (code "27") (name "Net-(DS1-SCL)") (class "Default")
      (node (ref "11") (pin "1") (pinfunction "1_1") (pintype "passive"))
      (node (ref "12") (pin "1") (pinfunction "1_1") (pintype "passive"))
      (node (ref "13") (pin "1") (pinfunction "1_1") (pintype "passive"))
      (node (ref "42") (pin "1") (pinfunction "1_1") (pintype "passive"))
      (node (ref "DS1") (pin "2") (pinfunction "SCL_2") (pintype "passive"))
      (node (ref "DS1") (pin "3") (pinfunction "SDA_3") (pintype "passive"))
      (node (ref "IC1") (pin "1") (pinfunction "7_1") (pintype "passive"))
      (node (ref "IC1") (pin "2") (pinfunction "6_2") (pintype "passive"))
      (node (ref "IC1") (pin "4") (pinfunction "4_4") (pintype "passive"))
      (node (ref "IC10") (pin "2") (pinfunction "DQ_2") (pintype "passive"))
      (node (ref "IC12") (pin "2") (pinfunction "DQ_2") (pintype "passive"))
      (node (ref "IC13") (pin "2") (pinfunction "DQ_2") (pintype "passive"))
      (node (ref "IC2") (pin "10") (pinfunction "RC0_10") (pintype "passive"))
      (node (ref "IC2") (pin "11") (pinfunction "RC2_11") (pintype "passive"))
      (node (ref "IC2") (pin "9") (pinfunction "RC1_9") (pintype "passive"))
      (node (ref "Z2") (pin "1") (pinfunction "K_1") (pintype "passive"))
      (node (ref "Z3") (pin "1") (pinfunction "K_1") (pintype "passive"))
      (node (ref "Z4") (pin "1") (pinfunction "K_1") (pintype "passive"))
    )
    (net (code "28") (name "Net-(IC1-0)") (class "Default")
      (node (ref "1") (pin "1") (pinfunction "1_1") (pintype "passive"))
      (node (ref "IC1") (pin "8") (pinfunction "0_8") (pintype "passive"))
    )
    (net (code "29") (name "Net-(IC1-1)") (class "Default")
      (node (ref "2") (pin "1") (pinfunction "1_1") (pintype "passive"))
      (node (ref "IC1") (pin "7") (pinfunction "1_7") (pintype "passive"))
    )
    (net (code "30") (name "Net-(IC1-2)") (class "Default")
      (node (ref "5") (pin "1") (pinfunction "1_1") (pintype "passive"))
      (node (ref "IC1") (pin "6") (pinfunction "2_6") (pintype "passive"))
    )
    (net (code "31") (name "Net-(IC1-3)") (class "Default")
      (node (ref "9") (pin "1") (pinfunction "1_1") (pintype "passive"))
      (node (ref "IC1") (pin "5") (pinfunction "3_5") (pintype "passive"))
    )
    (net (code "32") (name "Net-(IC1-5)") (class "Default")
      (node (ref "16") (pin "1") (pinfunction "1_1") (pintype "passive"))
      (node (ref "19") (pin "2") (pinfunction "2_2") (pintype "passive"))
      (node (ref "IC1") (pin "3") (pinfunction "5_3") (pintype "passive"))
    )
    (net (code "33") (name "Net-(IC1-CLK)") (class "Default")
      (node (ref "IC1") (pin "10") (pinfunction "CLK_10") (pintype "passive"))
      (node (ref "IC2") (pin "13") (pinfunction "RC3_13") (pintype "passive"))
    )
    (net (code "34") (name "Net-(IC1-DTA)") (class "Default")
      (node (ref "IC1") (pin "9") (pinfunction "DTA_9") (pintype "passive"))
      (node (ref "IC2") (pin "14") (pinfunction "RA5_14") (pintype "passive"))
    )
    (net (code "35") (name "Net-(IC1-LAT)") (class "Default")
      (node (ref "IC1") (pin "11") (pinfunction "LAT_11") (pintype "passive"))
      (node (ref "IC2") (pin "12") (pinfunction "RA4_12") (pintype "passive"))
    )
    (net (code "36") (name "Net-(IC2-RA0)") (class "Default")
      (node (ref "10") (pin "2") (pinfunction "2_2") (pintype "passive"))
      (node (ref "3") (pin "2") (pinfunction "2_2") (pintype "passive"))
      (node (ref "4") (pin "2") (pinfunction "2_2") (pintype "passive"))
      (node (ref "7") (pin "2") (pinfunction "2_2") (pintype "passive"))
      (node (ref "8") (pin "1") (pinfunction "1_1") (pintype "passive"))
      (node (ref "IC2") (pin "3") (pinfunction "RA0_3") (pintype "passive"))
      (node (ref "S1") (pin "2") (pinfunction "N.O._2_2") (pintype "passive"))
      (node (ref "Z1") (pin "1") (pinfunction "K_1") (pintype "passive"))
    )
    (net (code "37") (name "Net-(IC2-RA1)") (class "Default")
      (node (ref "17") (pin "1") (pinfunction "1_1") (pintype "passive"))
      (node (ref "21") (pin "2") (pinfunction "2_2") (pintype "passive"))
      (node (ref "24") (pin "2") (pinfunction "2_2") (pintype "passive"))
      (node (ref "IC2") (pin "4") (pinfunction "RA1_4") (pintype "passive"))
      (node (ref "S8") (pin "2") (pinfunction "N.O._2_2") (pintype "passive"))
      (node (ref "Z5") (pin "1") (pinfunction "K_1") (pintype "passive"))
    )
    (net (code "38") (name "Net-(IC2-RA2)") (class "Default")
      (node (ref "29") (pin "1") (pinfunction "1_1") (pintype "passive"))
      (node (ref "IC2") (pin "5") (pinfunction "RA2_5") (pintype "passive"))
      (node (ref "S10") (pin "2") (pinfunction "N.O._2_2") (pintype "passive"))
      (node (ref "Z6") (pin "1") (pinfunction "K_1") (pintype "passive"))
    )
    (net (code "39") (name "Net-(IC2-RC4)") (class "Default")
      (node (ref "39") (pin "2") (pinfunction "2_2") (pintype "passive"))
      (node (ref "IC2") (pin "8") (pinfunction "RC4_8") (pintype "passive"))
    )
    (net (code "40") (name "Net-(IC2-RC5)") (class "Default")
      (node (ref "41") (pin "2") (pinfunction "2_2") (pintype "passive"))
      (node (ref "IC2") (pin "6") (pinfunction "RC5_6") (pintype "passive"))
    )
    (net (code "41") (name "Net-(IC2-RST)") (class "Default")
      (node (ref "6") (pin "1") (pinfunction "1_1") (pintype "passive"))
      (node (ref "IC2") (pin "2") (pinfunction "RST_2") (pintype "passive"))
    )
    (net (code "42") (name "Net-(IC3-ANODE)") (class "Default")
      (node (ref "16") (pin "2") (pinfunction "2_2") (pintype "passive"))
      (node (ref "IC3") (pin "1") (pinfunction "ANODE_1") (pintype "passive"))
    )
    (net (code "43") (name "Net-(IC3-MAIN_TERM._1)") (class "Default")
      (node (ref "20") (pin "1") (pinfunction "1_1") (pintype "passive"))
      (node (ref "IC3") (pin "4") (pinfunction "MAIN_TERM._1_4") (pintype "passive"))
    )
    (net (code "44") (name "Net-(IC3-MAIN_TERM._2)") (class "Default")
      (node (ref "15") (pin "1") (pinfunction "1_1") (pintype "passive"))
      (node (ref "IC3") (pin "6") (pinfunction "MAIN_TERM._2_6") (pintype "passive"))
    )
    (net (code "45") (name "Net-(IC3-NC_2)") (class "Default")
      (node (ref "IC3") (pin "5") (pinfunction "NC_2_5") (pintype "passive"))
      (node (ref "IC4") (pin "2") (pinfunction "G_2") (pintype "passive"))
    )
    (net (code "46") (name "Net-(IC5-ANODE)") (class "Default")
      (node (ref "25") (pin "2") (pinfunction "2_2") (pintype "passive"))
      (node (ref "IC5") (pin "1") (pinfunction "ANODE_1") (pintype "passive"))
    )
    (net (code "47") (name "Net-(IC5-MAIN_TERM._1)") (class "Default")
      (node (ref "26") (pin "1") (pinfunction "1_1") (pintype "passive"))
      (node (ref "IC5") (pin "4") (pinfunction "MAIN_TERM._1_4") (pintype "passive"))
    )
    (net (code "48") (name "Net-(IC5-MAIN_TERM._2)") (class "Default")
      (node (ref "22") (pin "1") (pinfunction "1_1") (pintype "passive"))
      (node (ref "IC5") (pin "6") (pinfunction "MAIN_TERM._2_6") (pintype "passive"))
    )
    (net (code "49") (name "Net-(IC5-NC_2)") (class "Default")
      (node (ref "IC5") (pin "5") (pinfunction "NC_2_5") (pintype "passive"))
      (node (ref "IC6") (pin "2") (pinfunction "G_2") (pintype "passive"))
    )
    (net (code "50") (name "Net-(IC7-ANODE)") (class "Default")
      (node (ref "31") (pin "2") (pinfunction "2_2") (pintype "passive"))
      (node (ref "IC7") (pin "1") (pinfunction "ANODE_1") (pintype "passive"))
    )
    (net (code "51") (name "Net-(IC7-MAIN_TERM._1)") (class "Default")
      (node (ref "40") (pin "1") (pinfunction "1_1") (pintype "passive"))
      (node (ref "IC7") (pin "4") (pinfunction "MAIN_TERM._1_4") (pintype "passive"))
    )
    (net (code "52") (name "Net-(IC7-MAIN_TERM._2)") (class "Default")
      (node (ref "30") (pin "1") (pinfunction "1_1") (pintype "passive"))
      (node (ref "IC7") (pin "6") (pinfunction "MAIN_TERM._2_6") (pintype "passive"))
    )
    (net (code "53") (name "Net-(IC7-NC_2)") (class "Default")
      (node (ref "IC7") (pin "5") (pinfunction "NC_2_5") (pintype "passive"))
      (node (ref "IC8") (pin "2") (pinfunction "G_2") (pintype "passive"))
    )
    (net (code "54") (name "Net-(IC11-BST)") (class "Default")
      (node (ref "48") (pin "1") (pinfunction "1_1") (pintype "passive"))
      (node (ref "55") (pin "2") (pinfunction "2_2") (pintype "passive"))
      (node (ref "IC11") (pin "8") (pinfunction "BST_8") (pintype "passive"))
    )
    (net (code "55") (name "Net-(IC11-COMP)") (class "Default")
      (node (ref "47") (pin "2") (pinfunction "2_2") (pintype "passive"))
      (node (ref "IC11") (pin "3") (pinfunction "COMP_3") (pintype "passive"))
    )
    (net (code "56") (name "Net-(IC11-EN)") (class "Default")
      (node (ref "45") (pin "1") (pinfunction "1_1") (pintype "passive"))
      (node (ref "52") (pin "2") (pinfunction "2_2") (pintype "passive"))
      (node (ref "IC11") (pin "2") (pinfunction "EN_2") (pintype "passive"))
    )
    (net (code "57") (name "Net-(IC11-EP)") (class "Default")
      (node (ref "54") (pin "2") (pinfunction "2_2") (pintype "passive"))
      (node (ref "FL1") (pin "1") (pinfunction "1_1") (pintype "passive"))
      (node (ref "IC11") (pin "9") (pinfunction "EP_9") (pintype "passive"))
    )
    (net (code "58") (name "Net-(IC11-FREQ)") (class "Default")
      (node (ref "IC11") (pin "6") (pinfunction "FREQ_6") (pintype "passive"))
      (node (ref "U3") (pin "A1") (pinfunction "A1_A1") (pintype "passive"))
    )
    (net (code "59") (name "Net-(LED1-A)") (class "Default")
      (node (ref "1") (pin "2") (pinfunction "2_2") (pintype "passive"))
      (node (ref "LED1") (pin "2") (pinfunction "A_2") (pintype "passive"))
    )
    (net (code "60") (name "Net-(LED2-A)") (class "Default")
      (node (ref "2") (pin "2") (pinfunction "2_2") (pintype "passive"))
      (node (ref "LED2") (pin "2") (pinfunction "A_2") (pintype "passive"))
    )
    (net (code "61") (name "Net-(LED3-A)") (class "Default")
      (node (ref "5") (pin "2") (pinfunction "2_2") (pintype "passive"))
      (node (ref "LED3") (pin "2") (pinfunction "A_2") (pintype "passive"))
    )
    (net (code "62") (name "Net-(LED4-A)") (class "Default")
      (node (ref "9") (pin "2") (pinfunction "2_2") (pintype "passive"))
      (node (ref "LED4") (pin "2") (pinfunction "A_2") (pintype "passive"))
    )
    (net (code "63") (name "Net-(LED5-A)") (class "Default")
      (node (ref "19") (pin "1") (pinfunction "1_1") (pintype "passive"))
      (node (ref "LED5") (pin "2") (pinfunction "A_2") (pintype "passive"))
    )
    (net (code "64") (name "Net-(LED6-A)") (class "Default")
      (node (ref "27") (pin "1") (pinfunction "1_1") (pintype "passive"))
      (node (ref "LED6") (pin "2") (pinfunction "A_2") (pintype "passive"))
    )
    (net (code "65") (name "Net-(LED7-A)") (class "Default")
      (node (ref "35") (pin "1") (pinfunction "1_1") (pintype "passive"))
      (node (ref "LED7") (pin "2") (pinfunction "A_2") (pintype "passive"))
    )
    (net (code "66") (name "Net-(Q1-B)") (class "Default")
      (node (ref "42") (pin "2") (pinfunction "2_2") (pintype "passive"))
      (node (ref "Q1") (pin "1") (pinfunction "B_1") (pintype "passive"))
    )
    (net (code "67") (name "Net-(S2-N.O._2)") (class "Default")
      (node (ref "3") (pin "1") (pinfunction "1_1") (pintype "passive"))
      (node (ref "S2") (pin "2") (pinfunction "N.O._2_2") (pintype "passive"))
    )
    (net (code "68") (name "Net-(S3-N.O._2)") (class "Default")
      (node (ref "4") (pin "1") (pinfunction "1_1") (pintype "passive"))
      (node (ref "S3") (pin "2") (pinfunction "N.O._2_2") (pintype "passive"))
    )
    (net (code "69") (name "Net-(S4-N.O._2)") (class "Default")
      (node (ref "7") (pin "1") (pinfunction "1_1") (pintype "passive"))
      (node (ref "S4") (pin "2") (pinfunction "N.O._2_2") (pintype "passive"))
    )
    (net (code "70") (name "Net-(S5-N.O._2)") (class "Default")
      (node (ref "10") (pin "1") (pinfunction "1_1") (pintype "passive"))
      (node (ref "S5") (pin "2") (pinfunction "N.O._2_2") (pintype "passive"))
    )
    (net (code "71") (name "Net-(S6-N.O._2)") (class "Default")
      (node (ref "21") (pin "1") (pinfunction "1_1") (pintype "passive"))
      (node (ref "S6") (pin "2") (pinfunction "N.O._2_2") (pintype "passive"))
    )
    (net (code "72") (name "Net-(S7-N.O._2)") (class "Default")
      (node (ref "24") (pin "1") (pinfunction "1_1") (pintype "passive"))
      (node (ref "S7") (pin "2") (pinfunction "N.O._2_2") (pintype "passive"))
    )
    (net (code "73") (name "Net-(S10-N.O._1)") (class "Default")
      (node (ref "S10") (pin "1") (pinfunction "N.O._1_1") (pintype "passive"))
      (node (ref "S9") (pin "2") (pinfunction "N.O._2_2") (pintype "passive"))
    )
    (net (code "74") (name "Net-(S11-N.O._2)") (class "Default")
      (node (ref "S11") (pin "2") (pinfunction "N.O._2_2") (pintype "passive"))
      (node (ref "U2") (pin "B1") (pinfunction "B1_B1") (pintype "passive"))
    )
    (net (code "75") (name "Net-(U1-GP0)") (class "Default")
      (node (ref "34") (pin "1") (pinfunction "1_1") (pintype "passive"))
      (node (ref "U1") (pin "3") (pinfunction "GP0_3") (pintype "passive"))
    )
    (net (code "76") (name "Net-(U1-GP2)") (class "Default")
      (node (ref "37") (pin "1") (pinfunction "1_1") (pintype "passive"))
      (node (ref "U1") (pin "5") (pinfunction "GP2_5") (pintype "bidirectional"))
    )
    (net (code "77") (name "Net-(U1-GPIO15)") (class "Default")
      (node (ref "43") (pin "1") (pinfunction "1_1") (pintype "passive"))
      (node (ref "U1") (pin "30") (pinfunction "GPIO15_30") (pintype "bidirectional"))
    )
    (net (code "78") (name "Net-(U1-RST)") (class "Default")
      (node (ref "36") (pin "1") (pinfunction "1_1") (pintype "passive"))
      (node (ref "U1") (pin "4") (pinfunction "RST_4") (pintype "bidirectional"))
    )
    (net (code "79") (name "Net-(U1-RX)") (class "Default")
      (node (ref "39") (pin "1") (pinfunction "1_1") (pintype "passive"))
      (node (ref "U1") (pin "6") (pinfunction "RX_6") (pintype "bidirectional"))
    )
    (net (code "80") (name "Net-(U1-TX)") (class "Default")
      (node (ref "41") (pin "1") (pinfunction "1_1") (pintype "passive"))
      (node (ref "U1") (pin "7") (pinfunction "TX_7") (pintype "bidirectional"))
    )
    (net (code "81") (name "VDD3V3_1") (class "Default")
      (node (ref "U1") (pin "11") (pinfunction "VDD3V3_1_11") (pintype "power_in"))
    )
    (net (code "82") (name "VDD3V3_2") (class "Default")
      (node (ref "U1") (pin "16") (pinfunction "VDD3V3_2_16") (pintype "power_in"))
    )
    (net (code "83") (name "VDD3V3_3") (class "Default")
      (node (ref "U1") (pin "25") (pinfunction "VDD3V3_3_25") (pintype "power_in"))
    )
    (net (code "84") (name "VDD5V") (class "Default")
      (node (ref "U1") (pin "15") (pinfunction "VDD5V_15") (pintype "power_in"))
    )
    (net (code "85") (name "unconnected-(51-Pad2)") (class "Default")
      (node (ref "51") (pin "2") (pinfunction "2_2") (pintype "passive"))
    )
    (net (code "86") (name "unconnected-(DS1-BS0-Pad26)") (class "Default")
      (node (ref "DS1") (pin "26") (pinfunction "BS0_26") (pintype "passive"))
    )
    (net (code "87") (name "unconnected-(DS1-BS1-Pad27)") (class "Default")
      (node (ref "DS1") (pin "27") (pinfunction "BS1_27") (pintype "passive"))
    )
    (net (code "88") (name "unconnected-(DS1-CS-Pad29)") (class "Default")
      (node (ref "DS1") (pin "29") (pinfunction "CS_29") (pintype "passive"))
    )
    (net (code "89") (name "unconnected-(DS1-D0-Pad32)") (class "Default")
      (node (ref "DS1") (pin "32") (pinfunction "D0_32") (pintype "passive"))
    )
    (net (code "90") (name "unconnected-(DS1-D1-Pad33)") (class "Default")
      (node (ref "DS1") (pin "33") (pinfunction "D1_33") (pintype "passive"))
    )
    (net (code "91") (name "unconnected-(DS1-D2-Pad34)") (class "Default")
      (node (ref "DS1") (pin "34") (pinfunction "D2_34") (pintype "passive"))
    )
    (net (code "92") (name "unconnected-(DS1-D{slash}C-Pad31)") (class "Default")
      (node (ref "DS1") (pin "31") (pinfunction "D/C_31") (pintype "passive"))
    )
    (net (code "93") (name "unconnected-(DS1-ESD_GND_2-Pad20)") (class "Default")
      (node (ref "DS1") (pin "20") (pinfunction "ESD_GND_2_20") (pintype "passive"))
    )
    (net (code "94") (name "unconnected-(DS1-GND_1-Pad23)") (class "Default")
      (node (ref "DS1") (pin "23") (pinfunction "GND_1_23") (pintype "passive"))
    )
    (net (code "95") (name "unconnected-(DS1-GND_2-Pad24)") (class "Default")
      (node (ref "DS1") (pin "24") (pinfunction "GND_2_24") (pintype "passive"))
    )
    (net (code "96") (name "unconnected-(DS1-GND_3-Pad28)") (class "Default")
      (node (ref "DS1") (pin "28") (pinfunction "GND_3_28") (pintype "passive"))
    )
    (net (code "97") (name "unconnected-(DS1-GND_4-Pad35)") (class "Default")
      (node (ref "DS1") (pin "35") (pinfunction "GND_4_35") (pintype "passive"))
    )
    (net (code "98") (name "unconnected-(DS1-IREF-Pad36)") (class "Default")
      (node (ref "DS1") (pin "36") (pinfunction "IREF_36") (pintype "passive"))
    )
    (net (code "99") (name "unconnected-(DS1-NC_3-Pad18)") (class "Default")
      (node (ref "DS1") (pin "18") (pinfunction "NC_3_18") (pintype "passive"))
    )
    (net (code "100") (name "unconnected-(DS1-NC_4-Pad19)") (class "Default")
      (node (ref "DS1") (pin "19") (pinfunction "NC_4_19") (pintype "passive"))
    )
    (net (code "101") (name "unconnected-(DS1-RES-Pad30)") (class "Default")
      (node (ref "DS1") (pin "30") (pinfunction "RES_30") (pintype "passive"))
    )
    (net (code "102") (name "unconnected-(DS1-VCC_1-Pad21)") (class "Default")
      (node (ref "DS1") (pin "21") (pinfunction "VCC_1_21") (pintype "passive"))
    )
    (net (code "103") (name "unconnected-(DS1-VCC_2-Pad22)") (class "Default")
      (node (ref "DS1") (pin "22") (pinfunction "VCC_2_22") (pintype "passive"))
    )
    (net (code "104") (name "unconnected-(DS1-VCC_3-Pad39)") (class "Default")
      (node (ref "DS1") (pin "39") (pinfunction "VCC_3_39") (pintype "passive"))
    )
    (net (code "105") (name "unconnected-(DS1-VCOMH_1-Pad37)") (class "Default")
      (node (ref "DS1") (pin "37") (pinfunction "VCOMH_1_37") (pintype "passive"))
    )
    (net (code "106") (name "unconnected-(DS1-VCOMH_2-Pad38)") (class "Default")
      (node (ref "DS1") (pin "38") (pinfunction "VCOMH_2_38") (pintype "passive"))
    )
    (net (code "107") (name "unconnected-(DS1-VDD-Pad25)") (class "Default")
      (node (ref "DS1") (pin "25") (pinfunction "VDD_25") (pintype "passive"))
    )
    (net (code "108") (name "unconnected-(FL1-Pad2)") (class "Default")
      (node (ref "FL1") (pin "2") (pinfunction "2_2") (pintype "passive"))
    )
    (net (code "109") (name "unconnected-(FL1-Pad3)") (class "Default")
      (node (ref "FL1") (pin "3") (pinfunction "3_3") (pintype "passive"))
    )
    (net (code "110") (name "unconnected-(IC1-DS-Pad14)") (class "Default")
      (node (ref "IC1") (pin "14") (pinfunction "DS_14") (pintype "passive"))
    )
    (net (code "111") (name "unconnected-(IC1-Q0-Pad15)") (class "Default")
      (node (ref "IC1") (pin "15") (pinfunction "Q0_15") (pintype "passive"))
    )
    (net (code "112") (name "unconnected-(IC1-VCC-Pad16)") (class "Default")
      (node (ref "IC1") (pin "16") (pinfunction "VCC_16") (pintype "passive"))
    )
    (net (code "113") (name "unconnected-(IC2-RC3-Pad7)") (class "Default")
      (node (ref "IC2") (pin "7") (pinfunction "RC3_7") (pintype "passive"))
    )
    (net (code "114") (name "unconnected-(IC3-NC_1-Pad3)") (class "Default")
      (node (ref "IC3") (pin "3") (pinfunction "NC_1_3") (pintype "passive"))
    )
    (net (code "115") (name "unconnected-(IC5-NC_1-Pad3)") (class "Default")
      (node (ref "IC5") (pin "3") (pinfunction "NC_1_3") (pintype "passive"))
    )
    (net (code "116") (name "unconnected-(IC7-NC_1-Pad3)") (class "Default")
      (node (ref "IC7") (pin "3") (pinfunction "NC_1_3") (pintype "passive"))
    )
    (net (code "117") (name "unconnected-(IC11-FB-Pad4)") (class "Default")
      (node (ref "IC11") (pin "4") (pinfunction "FB_4") (pintype "passive"))
    )
    (net (code "118") (name "unconnected-(T1-NC-Pad5)") (class "Default")
      (node (ref "T1") (pin "5") (pinfunction "NC_5") (pintype "passive"))
    )
    (net (code "119") (name "unconnected-(T1-PRI_1-Pad1)") (class "Default")
      (node (ref "T1") (pin "1") (pinfunction "PRI_1_1") (pintype "passive"))
    )
    (net (code "120") (name "unconnected-(T1-PRI_2-Pad2)") (class "Default")
      (node (ref "T1") (pin "2") (pinfunction "PRI_2_2") (pintype "passive"))
    )
    (net (code "121") (name "unconnected-(T1-PRI_3-Pad3)") (class "Default")
      (node (ref "T1") (pin "3") (pinfunction "PRI_3_3") (pintype "passive"))
    )
    (net (code "122") (name "unconnected-(U1-D1_-_GPIO5-Pad29)") (class "Default")
      (node (ref "U1") (pin "29") (pinfunction "D1_-_GPIO5_29") (pintype "bidirectional"))
    )
    (net (code "123") (name "unconnected-(U1-D2_-_GPIO4-Pad28)") (class "Default")
      (node (ref "U1") (pin "28") (pinfunction "D2_-_GPIO4_28") (pintype "bidirectional"))
    )
    (net (code "124") (name "unconnected-(U1-D3_-_GPIO0-Pad27)") (class "Default")
      (node (ref "U1") (pin "27") (pinfunction "D3_-_GPIO0_27") (pintype "bidirectional"))
    )
    (net (code "125") (name "unconnected-(U1-D4_-_GPIO2_{slash}_TXD1-Pad26)") (class "Default")
      (node (ref "U1") (pin "26") (pinfunction "D4_-_GPIO2_/_TXD1_26") (pintype "bidirectional"))
    )
    (net (code "126") (name "unconnected-(U1-D5_-_GPIO14_{slash}_HSPICLK-Pad23)") (class "Default")
      (node (ref "U1") (pin "23") (pinfunction "D5_-_GPIO14_/_HSPICLK_23") (pintype "bidirectional"))
    )
    (net (code "127") (name "unconnected-(U1-D6_-_GPIO12_{slash}_HSPIQ-Pad22)") (class "Default")
      (node (ref "U1") (pin "22") (pinfunction "D6_-_GPIO12_/_HSPIQ_22") (pintype "bidirectional"))
    )
    (net (code "128") (name "unconnected-(U1-D7_-_GPIO13_{slash}_RXD2_{slash}_HSPID-Pad21)") (class "Default")
      (node (ref "U1") (pin "21") (pinfunction "D7_-_GPIO13_/_RXD2_/_HSPID_21") (pintype "bidirectional"))
    )
    (net (code "129") (name "unconnected-(U1-D8_-_GPIO15_{slash}_TXD2_{slash}_HSPICS-Pad20)") (class "Default")
      (node (ref "U1") (pin "20") (pinfunction "D8_-_GPIO15_/_TXD2_/_HSPICS_20") (pintype "bidirectional"))
    )
    (net (code "130") (name "unconnected-(U1-D9_-__RXD0_{slash}_GPIO3-Pad19)") (class "Default")
      (node (ref "U1") (pin "19") (pinfunction "D9_-__RXD0_/_GPIO3_19") (pintype "bidirectional"))
    )
    (net (code "131") (name "unconnected-(U1-D10_-_TXD0_{slash}_GPIO1-Pad18)") (class "Default")
      (node (ref "U1") (pin "18") (pinfunction "D10_-_TXD0_/_GPIO1_18") (pintype "bidirectional"))
    )
    (net (code "132") (name "unconnected-(U1-EN-Pad12)") (class "Default")
      (node (ref "U1") (pin "12") (pinfunction "EN_12") (pintype "input"))
    )
    (net (code "133") (name "unconnected-(U1-NRST-Pad13)") (class "Default")
      (node (ref "U1") (pin "13") (pinfunction "NRST_13") (pintype "input"))
    )
    (net (code "134") (name "unconnected-(U1-SPI_CLK_{slash}_SD_CLK-Pad9)") (class "Default")
      (node (ref "U1") (pin "9") (pinfunction "SPI_CLK_/_SD_CLK_9") (pintype "bidirectional"))
    )
    (net (code "135") (name "unconnected-(U2-PadA1)") (class "Default")
      (node (ref "U2") (pin "A1") (pinfunction "A1_A1") (pintype "passive"))
    )
    (net (code "136") (name "unconnected-(U2-PadB2)") (class "Default")
      (node (ref "U2") (pin "B2") (pinfunction "B2_B2") (pintype "passive"))
    )
    (net (code "137") (name "unconnected-(U3-PadA2)") (class "Default")
      (node (ref "U3") (pin "A2") (pinfunction "A2_A2") (pintype "passive"))
    )
    (net (code "138") (name "unconnected-(U3-PadB1)") (class "Default")
      (node (ref "U3") (pin "B1") (pinfunction "B1_B1") (pintype "passive"))
    )
  )
)
